# audio_codec.net
KiCad netlist of a schematic drawn in Altium Designer
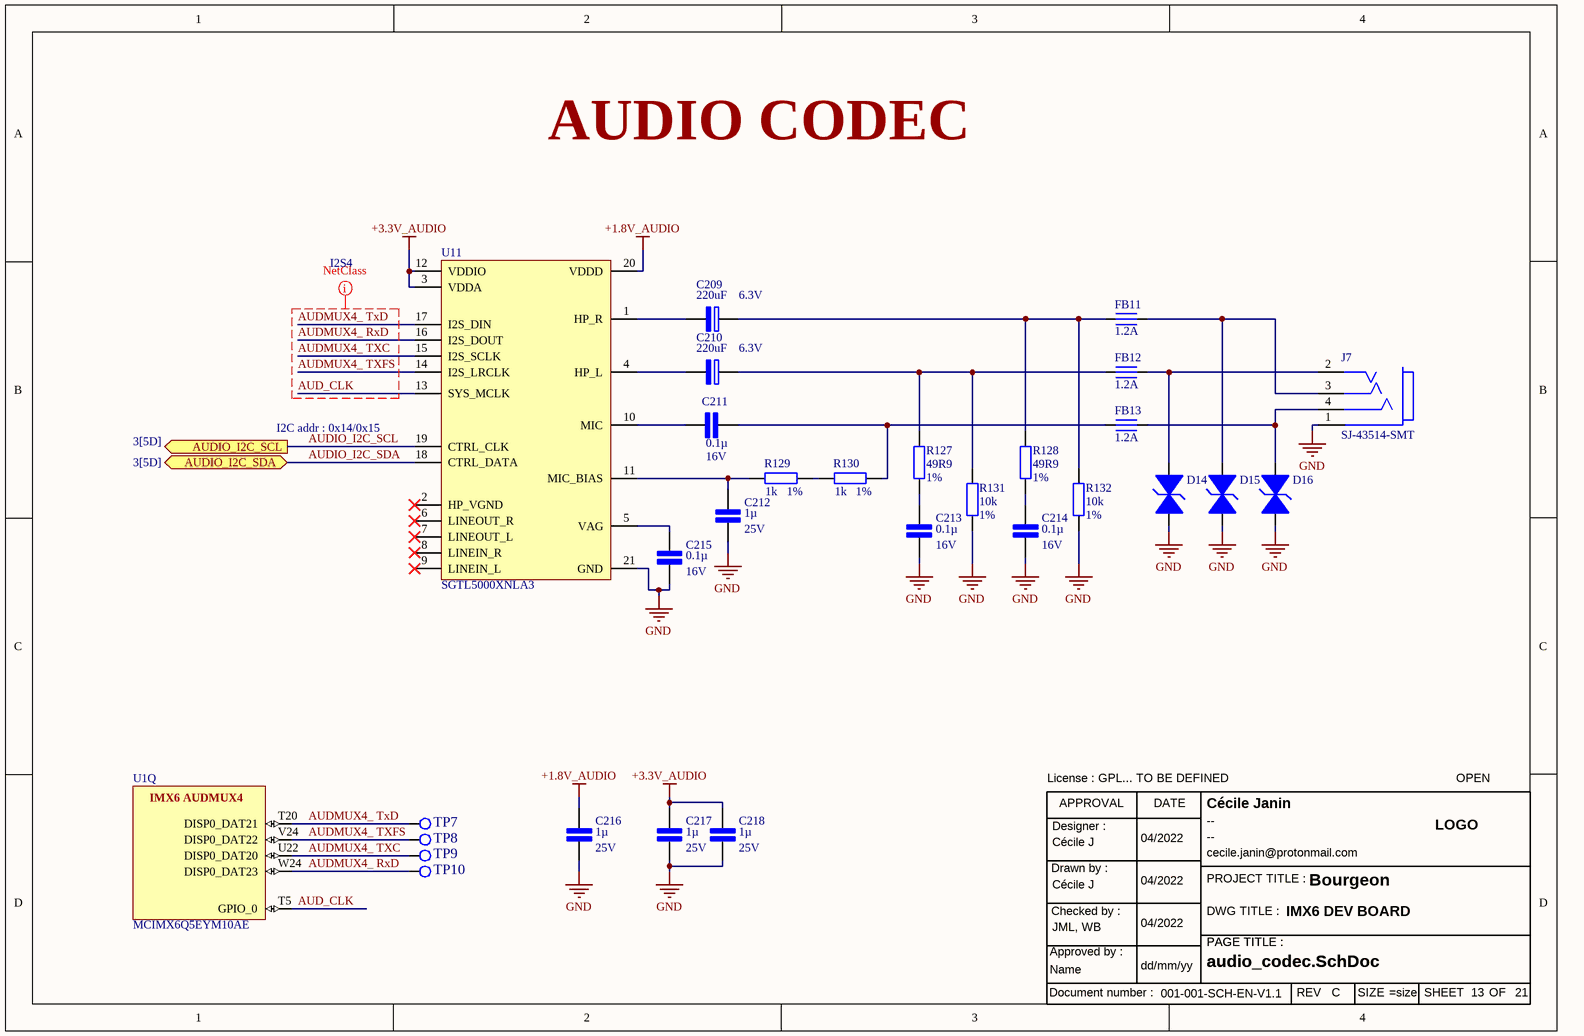
[diagram p0: audio_codec.SchDoc]

(export (version "E")
  (design (tool "Eeschema 10.0.6"))
  (components
    (comp (ref "C209")
      (value "220uF")
      (footprint "cap polymer wurth")
      (description "WCAP-PHGP Aluminum Polymer Capacitor, H-Chip SMT, L7.3W4.3H1.9mm, 220uF, 6.3V 875015119006")
      (fields
        (field (name "MANUFACTURER") "Wurth Elektronik")
        (field (name "MANUFACTURER PART NUMBER") "875015119006")
        (field (name "RATED VOLTAGE (DC)") "6.3V")
      )
      (libsource (lib "First Board IMX6") (part "cap 220µ 6.3V"))
    )
    (comp (ref "C210")
      (value "220uF")
      (footprint "cap polymer wurth")
      (description "WCAP-PHGP Aluminum Polymer Capacitor, H-Chip SMT, L7.3W4.3H1.9mm, 220uF, 6.3V 875015119006")
      (fields
        (field (name "MANUFACTURER") "Wurth Elektronik")
        (field (name "MANUFACTURER PART NUMBER") "875015119006")
        (field (name "RATED VOLTAGE (DC)") "6.3V")
      )
      (libsource (lib "First Board IMX6") (part "cap 220µ 6.3V"))
    )
    (comp (ref "C211")
      (value "0.1µ")
      (footprint "Cap cer 0402/1005")
      (description "cap solid electrolyte 0.1µ 6.3V 10%")
      (fields (field (name "TENSION DU DIÉLECTRIQUE") "16V"))
      (libsource (lib "") (part "cap 0.1µ 16V_1"))
    )
    (comp (ref "C212")
      (value "1µ")
      (footprint "Cap cer 0402/1005")
      (description "cap cer 1µ 25V 10% X5R 0402")
      (fields (field (name "TENSION DU DIÉLECTRIQUE") "25V"))
      (libsource (lib "First Board IMX6") (part "cap 1µ 25V"))
    )
    (comp (ref "C213")
      (value "0.1µ")
      (footprint "Cap cer 0402/1005")
      (description "cap solid electrolyte 0.1µ 6.3V 10%")
      (fields (field (name "TENSION DU DIÉLECTRIQUE") "16V"))
      (libsource (lib "First Board IMX6") (part "cap 0.1µ 16V"))
    )
    (comp (ref "C214")
      (value "0.1µ")
      (footprint "Cap cer 0402/1005")
      (description "cap solid electrolyte 0.1µ 6.3V 10%")
      (fields (field (name "TENSION DU DIÉLECTRIQUE") "16V"))
      (libsource (lib "First Board IMX6") (part "cap 0.1µ 16V"))
    )
    (comp (ref "C215")
      (value "0.1µ")
      (footprint "Cap cer 0402/1005")
      (description "cap solid electrolyte 0.1µ 6.3V 10%")
      (fields (field (name "TENSION DU DIÉLECTRIQUE") "16V"))
      (libsource (lib "First Board IMX6") (part "cap 0.1µ 16V"))
    )
    (comp (ref "C216")
      (value "1µ")
      (footprint "Cap cer 0402/1005")
      (description "cap cer 1µ 25V 10% X5R 0402")
      (fields (field (name "TENSION DU DIÉLECTRIQUE") "25V"))
      (libsource (lib "First Board IMX6") (part "cap 1µ 25V"))
    )
    (comp (ref "C217")
      (value "1µ")
      (footprint "Cap cer 0402/1005")
      (description "cap cer 1µ 25V 10% X5R 0402")
      (fields (field (name "TENSION DU DIÉLECTRIQUE") "25V"))
      (libsource (lib "First Board IMX6") (part "cap 1µ 25V"))
    )
    (comp (ref "C218")
      (value "1µ")
      (footprint "Cap cer 0402/1005")
      (description "cap cer 1µ 25V 10% X5R 0402")
      (fields (field (name "TENSION DU DIÉLECTRIQUE") "25V"))
      (libsource (lib "First Board IMX6") (part "cap 1µ 25V"))
    )
    (comp (ref "D14")
      (value "TVS 5V")
      (footprint "inductor 0402/1005")
      (description "82357120050")
      (libsource (lib "First Board IMX6") (part "TVS suppressor 82357120050"))
    )
    (comp (ref "D15")
      (value "TVS 5V")
      (footprint "inductor 0402/1005")
      (description "82357120050")
      (libsource (lib "First Board IMX6") (part "TVS suppressor 82357120050"))
    )
    (comp (ref "D16")
      (value "TVS 5V")
      (footprint "inductor 0402/1005")
      (description "82357120050")
      (libsource (lib "First Board IMX6") (part "TVS suppressor 82357120050"))
    )
    (comp (ref "FB11")
      (value "1.2A")
      (footprint "inductor 0402/1005")
      (description "ferrite bead 1.2A 70mohm\r\n74269242111")
      (libsource (lib "First Board IMX6") (part "Ferrite bead 0402"))
    )
    (comp (ref "FB12")
      (value "1.2A")
      (footprint "inductor 0402/1005")
      (description "ferrite bead 1.2A 70mohm\r\n74269242111")
      (libsource (lib "First Board IMX6") (part "Ferrite bead 0402"))
    )
    (comp (ref "FB13")
      (value "1.2A")
      (footprint "inductor 0402/1005")
      (description "ferrite bead 1.2A 70mohm\r\n74269242111")
      (libsource (lib "First Board IMX6") (part "Ferrite bead 0402"))
    )
    (comp (ref "J7")
      (value "SJ-43514-SMT")
      (footprint "Jack SJ-43514-SMT")
      (description "4 pole audio Jack SJ-43514-SMT")
      (libsource (lib "First Board IMX6") (part "Audio Jack 3.5mm 4 pin"))
    )
    (comp (ref "R127")
      (value "49R9")
      (footprint "Res 0402/1005")
      (description "res 49R9 ohm 1% 0402")
      (fields (field (name "POURCENTAGE") "1%"))
      (libsource (lib "First Board IMX6") (part "res 49R9 1%"))
    )
    (comp (ref "R128")
      (value "49R9")
      (footprint "Res 0402/1005")
      (description "res 49R9 ohm 1% 0402")
      (fields (field (name "POURCENTAGE") "1%"))
      (libsource (lib "First Board IMX6") (part "res 49R9 1%"))
    )
    (comp (ref "R129")
      (value "1k")
      (footprint "Res 0402/1005")
      (description "res 1k 1% 0402")
      (fields (field (name "POURCENTAGE") "1%"))
      (libsource (lib "First Board IMX6") (part "res 1k 1%"))
    )
    (comp (ref "R130")
      (value "1k")
      (footprint "Res 0402/1005")
      (description "res 1k 1% 0402")
      (fields (field (name "POURCENTAGE") "1%"))
      (libsource (lib "First Board IMX6") (part "res 1k 1%"))
    )
    (comp (ref "R131")
      (value "10k")
      (footprint "Res 0402/1005")
      (description "res 10k 1% 0402")
      (fields (field (name "POURCENTAGE") "1%"))
      (libsource (lib "First Board IMX6") (part "res 10k 1%"))
    )
    (comp (ref "R132")
      (value "10k")
      (footprint "Res 0402/1005")
      (description "res 10k 1% 0402")
      (fields (field (name "POURCENTAGE") "1%"))
      (libsource (lib "First Board IMX6") (part "res 10k 1%"))
    )
    (comp (ref "TB12")
      (value "Title bloc ANSI modified")
      (libsource (lib "First Board IMX6") (part "Title bloc ANSI"))
    )
    (comp (ref "TP7")
      (value "Test Point")
      (footprint "testpoint 1mm")
      (description "Test point 1mm diameter")
      (libsource (lib "First Board IMX6") (part "Test Point"))
    )
    (comp (ref "TP8")
      (value "Test Point")
      (footprint "testpoint 1mm")
      (description "Test point 1mm diameter")
      (libsource (lib "First Board IMX6") (part "Test Point"))
    )
    (comp (ref "TP9")
      (value "Test Point")
      (footprint "testpoint 1mm")
      (description "Test point 1mm diameter")
      (libsource (lib "First Board IMX6") (part "Test Point"))
    )
    (comp (ref "TP10")
      (value "Test Point")
      (footprint "testpoint 1mm")
      (description "Test point 1mm diameter")
      (libsource (lib "First Board IMX6") (part "Test Point"))
    )
    (comp (ref "U1")
      (value "MCIMX6Q5EYM10AE")
      (footprint "FRES-2197-01")
      (fields
        (field (name "PARTNUMBER") "MCIMX6Q5EYM10ACR")
        (field (name "MANUFACTURER") "Freescale Semiconductor")
      )
      (libsource (lib "First Board IMX6") (part "IMX6Q5EYM10AE"))
    )
    (comp (ref "U11")
      (value "SGTL5000XNLA3")
      (footprint "QFN20")
      (description "Audio codec")
      (libsource (lib "First Board IMX6") (part "IC SGTL5000XNLA3"))
    )
  )
  (nets
    (net (code "1") (name "+1.8V_AUDIO") (class "Default")
      (node (ref "C216") (pin "2") (pinfunction "4_2") (pintype "passive"))
      (node (ref "U11") (pin "20") (pinfunction "VDDD_20") (pintype "passive"))
    )
    (net (code "2") (name "+3.3V_AUDIO") (class "Default")
      (node (ref "C217") (pin "2") (pinfunction "4_2") (pintype "passive"))
      (node (ref "C218") (pin "2") (pinfunction "4_2") (pintype "passive"))
      (node (ref "U11") (pin "12") (pinfunction "VDDIO_12") (pintype "passive"))
      (node (ref "U11") (pin "3") (pinfunction "VDDA_3") (pintype "passive"))
    )
    (net (code "3") (name "/AUDIO_I2C_SCL") (class "Default")
      (node (ref "U11") (pin "19") (pinfunction "CTRL_CLK_19") (pintype "passive"))
    )
    (net (code "4") (name "/AUDIO_I2C_SDA") (class "Default")
      (node (ref "U11") (pin "18") (pinfunction "CTRL_DATA_18") (pintype "passive"))
    )
    (net (code "5") (name "/AUDMUX4_ RxD") (class "Default")
      (node (ref "TP10") (pin "1") (pinfunction "tp_1") (pintype "passive"))
      (node (ref "U1") (pin "W24") (pinfunction "DISP0_DAT23_W24") (pintype "bidirectional"))
      (node (ref "U11") (pin "16") (pinfunction "I2S_DOUT_16") (pintype "passive"))
    )
    (net (code "6") (name "/AUDMUX4_ TXC") (class "Default")
      (node (ref "TP9") (pin "1") (pinfunction "tp_1") (pintype "passive"))
      (node (ref "U1") (pin "U22") (pinfunction "DISP0_DAT20_U22") (pintype "bidirectional"))
      (node (ref "U11") (pin "15") (pinfunction "I2S_SCLK_15") (pintype "passive"))
    )
    (net (code "7") (name "/AUDMUX4_ TXFS") (class "Default")
      (node (ref "TP8") (pin "1") (pinfunction "tp_1") (pintype "passive"))
      (node (ref "U1") (pin "V24") (pinfunction "DISP0_DAT22_V24") (pintype "bidirectional"))
      (node (ref "U11") (pin "14") (pinfunction "I2S_LRCLK_14") (pintype "passive"))
    )
    (net (code "8") (name "/AUDMUX4_ TxD") (class "Default")
      (node (ref "TP7") (pin "1") (pinfunction "tp_1") (pintype "passive"))
      (node (ref "U1") (pin "T20") (pinfunction "DISP0_DAT21_T20") (pintype "bidirectional"))
      (node (ref "U11") (pin "17") (pinfunction "I2S_DIN_17") (pintype "passive"))
    )
    (net (code "9") (name "/AUD_CLK") (class "Default")
      (node (ref "U1") (pin "T5") (pinfunction "GPIO_0_T5") (pintype "bidirectional"))
      (node (ref "U11") (pin "13") (pinfunction "SYS_MCLK_13") (pintype "passive"))
    )
    (net (code "10") (name "GND") (class "Default")
      (node (ref "C212") (pin "1") (pinfunction "3_1") (pintype "passive"))
      (node (ref "C213") (pin "2") (pinfunction "4_2") (pintype "passive"))
      (node (ref "C214") (pin "2") (pinfunction "4_2") (pintype "passive"))
      (node (ref "C215") (pin "2") (pinfunction "4_2") (pintype "passive"))
      (node (ref "C216") (pin "1") (pinfunction "3_1") (pintype "passive"))
      (node (ref "C217") (pin "1") (pinfunction "3_1") (pintype "passive"))
      (node (ref "C218") (pin "1") (pinfunction "3_1") (pintype "passive"))
      (node (ref "D14") (pin "2") (pintype "passive"))
      (node (ref "D15") (pin "2") (pintype "passive"))
      (node (ref "D16") (pin "2") (pintype "passive"))
      (node (ref "J7") (pin "1") (pinfunction "sleeve_1") (pintype "passive"))
      (node (ref "R131") (pin "1") (pintype "passive"))
      (node (ref "R132") (pin "1") (pintype "passive"))
      (node (ref "U11") (pin "21") (pinfunction "GND_21") (pintype "passive"))
    )
    (net (code "11") (name "Net-(C209-N)") (class "Default")
      (node (ref "C209") (pin "2") (pinfunction "N_2") (pintype "passive"))
      (node (ref "U11") (pin "1") (pinfunction "HP_R_1") (pintype "passive"))
    )
    (net (code "12") (name "Net-(C209-P)") (class "Default")
      (node (ref "C209") (pin "1") (pinfunction "P_1") (pintype "passive"))
      (node (ref "FB11") (pin "1") (pinfunction "1_1") (pintype "passive"))
      (node (ref "R128") (pin "2") (pintype "passive"))
      (node (ref "R132") (pin "2") (pintype "passive"))
    )
    (net (code "13") (name "Net-(C210-N)") (class "Default")
      (node (ref "C210") (pin "2") (pinfunction "N_2") (pintype "passive"))
      (node (ref "U11") (pin "4") (pinfunction "HP_L_4") (pintype "passive"))
    )
    (net (code "14") (name "Net-(C210-P)") (class "Default")
      (node (ref "C210") (pin "1") (pinfunction "P_1") (pintype "passive"))
      (node (ref "FB12") (pin "1") (pinfunction "1_1") (pintype "passive"))
      (node (ref "R127") (pin "2") (pintype "passive"))
      (node (ref "R131") (pin "2") (pintype "passive"))
    )
    (net (code "15") (name "Net-(C211-3)") (class "Default")
      (node (ref "C211") (pin "1") (pinfunction "3_1") (pintype "passive"))
      (node (ref "U11") (pin "10") (pinfunction "MIC_10") (pintype "passive"))
    )
    (net (code "16") (name "Net-(C211-4)") (class "Default")
      (node (ref "C211") (pin "2") (pinfunction "4_2") (pintype "passive"))
      (node (ref "FB13") (pin "1") (pinfunction "1_1") (pintype "passive"))
      (node (ref "R130") (pin "2") (pintype "passive"))
    )
    (net (code "17") (name "Net-(C212-4)") (class "Default")
      (node (ref "C212") (pin "2") (pinfunction "4_2") (pintype "passive"))
      (node (ref "R129") (pin "1") (pintype "passive"))
      (node (ref "U11") (pin "11") (pinfunction "MIC_BIAS_11") (pintype "passive"))
    )
    (net (code "18") (name "Net-(C213-3)") (class "Default")
      (node (ref "C213") (pin "1") (pinfunction "3_1") (pintype "passive"))
      (node (ref "R127") (pin "1") (pintype "passive"))
    )
    (net (code "19") (name "Net-(C214-3)") (class "Default")
      (node (ref "C214") (pin "1") (pinfunction "3_1") (pintype "passive"))
      (node (ref "R128") (pin "1") (pintype "passive"))
    )
    (net (code "20") (name "Net-(C215-3)") (class "Default")
      (node (ref "C215") (pin "1") (pinfunction "3_1") (pintype "passive"))
      (node (ref "U11") (pin "5") (pinfunction "VAG_5") (pintype "passive"))
    )
    (net (code "21") (name "Net-(J7-ring_1)") (class "Default")
      (node (ref "D15") (pin "1") (pintype "passive"))
      (node (ref "FB11") (pin "2") (pinfunction "2_2") (pintype "passive"))
      (node (ref "J7") (pin "3") (pinfunction "ring_1_3") (pintype "passive"))
    )
    (net (code "22") (name "Net-(J7-ring_2)") (class "Default")
      (node (ref "D16") (pin "1") (pintype "passive"))
      (node (ref "FB13") (pin "2") (pinfunction "2_2") (pintype "passive"))
      (node (ref "J7") (pin "4") (pinfunction "ring_2_4") (pintype "passive"))
    )
    (net (code "23") (name "Net-(J7-tip)") (class "Default")
      (node (ref "D14") (pin "1") (pintype "passive"))
      (node (ref "FB12") (pin "2") (pinfunction "2_2") (pintype "passive"))
      (node (ref "J7") (pin "2") (pinfunction "tip_2") (pintype "passive"))
    )
    (net (code "24") (name "Net-(R129-Pad2)") (class "Default")
      (node (ref "R129") (pin "2") (pintype "passive"))
      (node (ref "R130") (pin "1") (pintype "passive"))
    )
    (net (code "25") (name "unconnected-(U11-HP_VGND-Pad2)") (class "Default")
      (node (ref "U11") (pin "2") (pinfunction "HP_VGND_2") (pintype "passive+no_connect"))
    )
    (net (code "26") (name "unconnected-(U11-LINEIN_L-Pad9)") (class "Default")
      (node (ref "U11") (pin "9") (pinfunction "LINEIN_L_9") (pintype "passive+no_connect"))
    )
    (net (code "27") (name "unconnected-(U11-LINEIN_R-Pad8)") (class "Default")
      (node (ref "U11") (pin "8") (pinfunction "LINEIN_R_8") (pintype "passive+no_connect"))
    )
    (net (code "28") (name "unconnected-(U11-LINEOUT_L-Pad7)") (class "Default")
      (node (ref "U11") (pin "7") (pinfunction "LINEOUT_L_7") (pintype "passive+no_connect"))
    )
    (net (code "29") (name "unconnected-(U11-LINEOUT_R-Pad6)") (class "Default")
      (node (ref "U11") (pin "6") (pinfunction "LINEOUT_R_6") (pintype "passive+no_connect"))
    )
  )
)
